# GPS_L80.net
KiCad netlist of a schematic drawn in Altium Designer
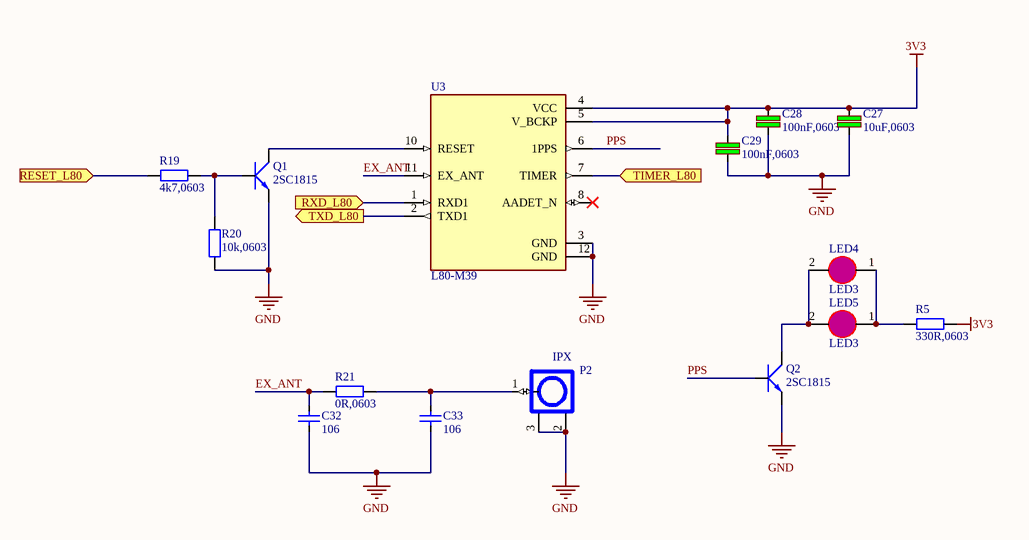
[diagram p0: GPS_L80.SchDoc]

(export (version "E")
  (design (tool "Eeschema 10.0.6"))
  (components
    (comp (ref "C27")
      (value "10uF,0603")
      (footprint "CAP_0603")
      (description "4.7µF ±10% 35V Ceramic Capacitor X5R 0805 (2012 Metric)")
      (fields
        (field (name "MANUFACTURER") "Samsung Electro-Mechanics")
        (field (name "PART NUMBER") "CL21A475KLCLQNC")
      )
      (libsource (lib "Anh_Trung") (part "C"))
    )
    (comp (ref "C28")
      (value "100nF,0603")
      (footprint "CAP_0603")
      (description "4.7µF ±10% 35V Ceramic Capacitor X5R 0805 (2012 Metric)")
      (fields
        (field (name "MANUFACTURER") "Samsung Electro-Mechanics")
        (field (name "PART NUMBER") "CL21A475KLCLQNC")
      )
      (libsource (lib "Anh_Trung") (part "C"))
    )
    (comp (ref "C29")
      (value "100nF,0603")
      (footprint "CAP_0603")
      (description "4.7µF ±10% 35V Ceramic Capacitor X5R 0805 (2012 Metric)")
      (fields
        (field (name "MANUFACTURER") "Samsung Electro-Mechanics")
        (field (name "PART NUMBER") "CL21A475KLCLQNC")
      )
      (libsource (lib "Anh_Trung") (part "C"))
    )
    (comp (ref "C32")
      (value "106")
      (footprint "CAP_0603")
      (description "Capacitor")
      (fields (field (name "PUBLISHER") "Altium Limited"))
      (libsource (lib "My Library") (part "CapSMD"))
    )
    (comp (ref "C33")
      (value "106")
      (footprint "CAP_0603")
      (description "Capacitor")
      (fields (field (name "PUBLISHER") "Altium Limited"))
      (libsource (lib "My Library") (part "CapSMD"))
    )
    (comp (ref "LED4")
      (value "LED3")
      (footprint "LED0805")
      (description "LED SMD 0805")
      (libsource (lib "My Library 2") (part "LED0805"))
    )
    (comp (ref "LED5")
      (value "LED3")
      (footprint "LED0805")
      (description "LED SMD 0805")
      (libsource (lib "My Library 2") (part "LED0805"))
    )
    (comp (ref "P2")
      (value "IPX")
      (footprint "IPXS")
      (description "Antenna GSM GPS")
      (fields
        (field (name "MANUFACTURER") "TE Connectivity AMP Connectors")
        (field (name "PART NUMBER") "2334884-1")
      )
      (libsource (lib "Anh_Trung") (part "IPXSx66"))
    )
    (comp (ref "Q1")
      (value "2SC1815")
      (footprint "SOT23")
      (description "NPN 600mW, ECB")
      (libsource (lib "My Library 2") (part "2SC1815"))
    )
    (comp (ref "Q2")
      (value "2SC1815")
      (footprint "SOT23-321")
      (description "NPN 600mW, ECB")
      (libsource (lib "My Library 2") (part "2SC1815"))
    )
    (comp (ref "R5")
      (value "330R,0603")
      (footprint "RES-SMD-0603")
      (description "Resistor SMD")
      (fields
        (field (name "MANUFACTURER") "Generic Components")
        (field (name "PUBLISHER") "Altium Hobart Technology Centre")
      )
      (libsource (lib "My Library") (part "Resistor - SMD"))
    )
    (comp (ref "R19")
      (value "4k7,0603")
      (footprint "RES-SMD-0603")
      (description "Resistor SMD")
      (fields
        (field (name "MANUFACTURER") "Generic Components")
        (field (name "PUBLISHER") "Altium Hobart Technology Centre")
      )
      (libsource (lib "My Library") (part "Resistor - SMD"))
    )
    (comp (ref "R20")
      (value "10k,0603")
      (footprint "RES-SMD-0603")
      (description "Resistor SMD")
      (fields
        (field (name "MANUFACTURER") "Generic Components")
        (field (name "PUBLISHER") "Altium Hobart Technology Centre")
      )
      (libsource (lib "My Library") (part "Resistor - SMD"))
    )
    (comp (ref "R21")
      (value "0R,0603")
      (footprint "RES-SMD-0603")
      (description "Resistor SMD")
      (fields
        (field (name "MANUFACTURER") "Generic Components")
        (field (name "PUBLISHER") "Altium Hobart Technology Centre")
      )
      (libsource (lib "My Library") (part "Resistor - SMD"))
    )
    (comp (ref "U3")
      (value "L80-M39")
      (footprint "XCVR_L80-M39")
      (fields (field (name "MF") "Quectel"))
      (libsource (lib "L80-M39") (part "L80-M39"))
    )
  )
  (nets
    (net (code "1") (name "/EX_ANT") (class "Default")
      (node (ref "C32") (pin "2") (pinfunction "2_2") (pintype "passive"))
      (node (ref "R21") (pin "2") (pinfunction "2_2") (pintype "passive"))
      (node (ref "U3") (pin "11") (pinfunction "EX_ANT_11") (pintype "input"))
    )
    (net (code "2") (name "/PPS") (class "Default")
      (node (ref "Q2") (pin "3") (pinfunction "B_3") (pintype "passive"))
      (node (ref "U3") (pin "6") (pinfunction "1PPS_6") (pintype "output"))
    )
    (net (code "3") (name "/RESET_L80") (class "Default")
      (node (ref "R19") (pin "2") (pinfunction "2_2") (pintype "passive"))
    )
    (net (code "4") (name "/RXD_L80") (class "Default")
      (node (ref "U3") (pin "1") (pinfunction "RXD1_1") (pintype "input"))
    )
    (net (code "5") (name "/TIMER_L80") (class "Default")
      (node (ref "U3") (pin "7") (pinfunction "TIMER_7") (pintype "output"))
    )
    (net (code "6") (name "/TXD_L80") (class "Default")
      (node (ref "U3") (pin "2") (pinfunction "TXD1_2") (pintype "output"))
    )
    (net (code "7") (name "3V3") (class "Default")
      (node (ref "C27") (pin "2") (pinfunction "2_2") (pintype "passive"))
      (node (ref "C28") (pin "2") (pinfunction "2_2") (pintype "passive"))
      (node (ref "C29") (pin "2") (pinfunction "2_2") (pintype "passive"))
      (node (ref "R5") (pin "1") (pinfunction "1_1") (pintype "passive"))
      (node (ref "U3") (pin "4") (pinfunction "VCC_4") (pintype "power_in"))
      (node (ref "U3") (pin "5") (pinfunction "V_BCKP_5") (pintype "power_in"))
    )
    (net (code "8") (name "GND") (class "Default")
      (node (ref "C27") (pin "1") (pinfunction "1_1") (pintype "passive"))
      (node (ref "C28") (pin "1") (pinfunction "1_1") (pintype "passive"))
      (node (ref "C29") (pin "1") (pinfunction "1_1") (pintype "passive"))
      (node (ref "C32") (pin "1") (pinfunction "1_1") (pintype "passive"))
      (node (ref "C33") (pin "1") (pinfunction "1_1") (pintype "passive"))
      (node (ref "P2") (pin "2") (pintype "passive"))
      (node (ref "P2") (pin "3") (pintype "passive"))
      (node (ref "Q1") (pin "1") (pinfunction "E_1") (pintype "passive"))
      (node (ref "Q2") (pin "1") (pinfunction "E_1") (pintype "passive"))
      (node (ref "R20") (pin "1") (pinfunction "1_1") (pintype "passive"))
      (node (ref "U3") (pin "12") (pinfunction "GND_12") (pintype "power_in"))
      (node (ref "U3") (pin "3") (pinfunction "GND_3") (pintype "power_in"))
    )
    (net (code "9") (name "Net-(C33-Pad2)") (class "Default")
      (node (ref "C33") (pin "2") (pinfunction "2_2") (pintype "passive"))
      (node (ref "P2") (pin "1") (pintype "bidirectional"))
      (node (ref "R21") (pin "1") (pinfunction "1_1") (pintype "passive"))
    )
    (net (code "10") (name "Net-(LED4-A)") (class "Default")
      (node (ref "LED4") (pin "1") (pinfunction "A_1") (pintype "passive"))
      (node (ref "LED5") (pin "1") (pinfunction "A_1") (pintype "passive"))
      (node (ref "R5") (pin "2") (pinfunction "2_2") (pintype "passive"))
    )
    (net (code "11") (name "Net-(LED4-K)") (class "Default")
      (node (ref "LED4") (pin "2") (pinfunction "K_2") (pintype "passive"))
      (node (ref "LED5") (pin "2") (pinfunction "K_2") (pintype "passive"))
      (node (ref "Q2") (pin "2") (pinfunction "C_2") (pintype "passive"))
    )
    (net (code "12") (name "Net-(Q1-B)") (class "Default")
      (node (ref "Q1") (pin "3") (pinfunction "B_3") (pintype "passive"))
      (node (ref "R19") (pin "1") (pinfunction "1_1") (pintype "passive"))
      (node (ref "R20") (pin "2") (pinfunction "2_2") (pintype "passive"))
    )
    (net (code "13") (name "Net-(Q1-C)") (class "Default")
      (node (ref "Q1") (pin "2") (pinfunction "C_2") (pintype "passive"))
      (node (ref "U3") (pin "10") (pinfunction "RESET_10") (pintype "input"))
    )
    (net (code "14") (name "unconnected-(U3-AADET_N-Pad8)") (class "Default")
      (node (ref "U3") (pin "8") (pinfunction "AADET_N_8") (pintype "bidirectional+no_connect"))
    )
  )
)
